# SCH_automated_chess_2024-11-14.net
KiCad netlist of a schematic drawn in EasyEDA
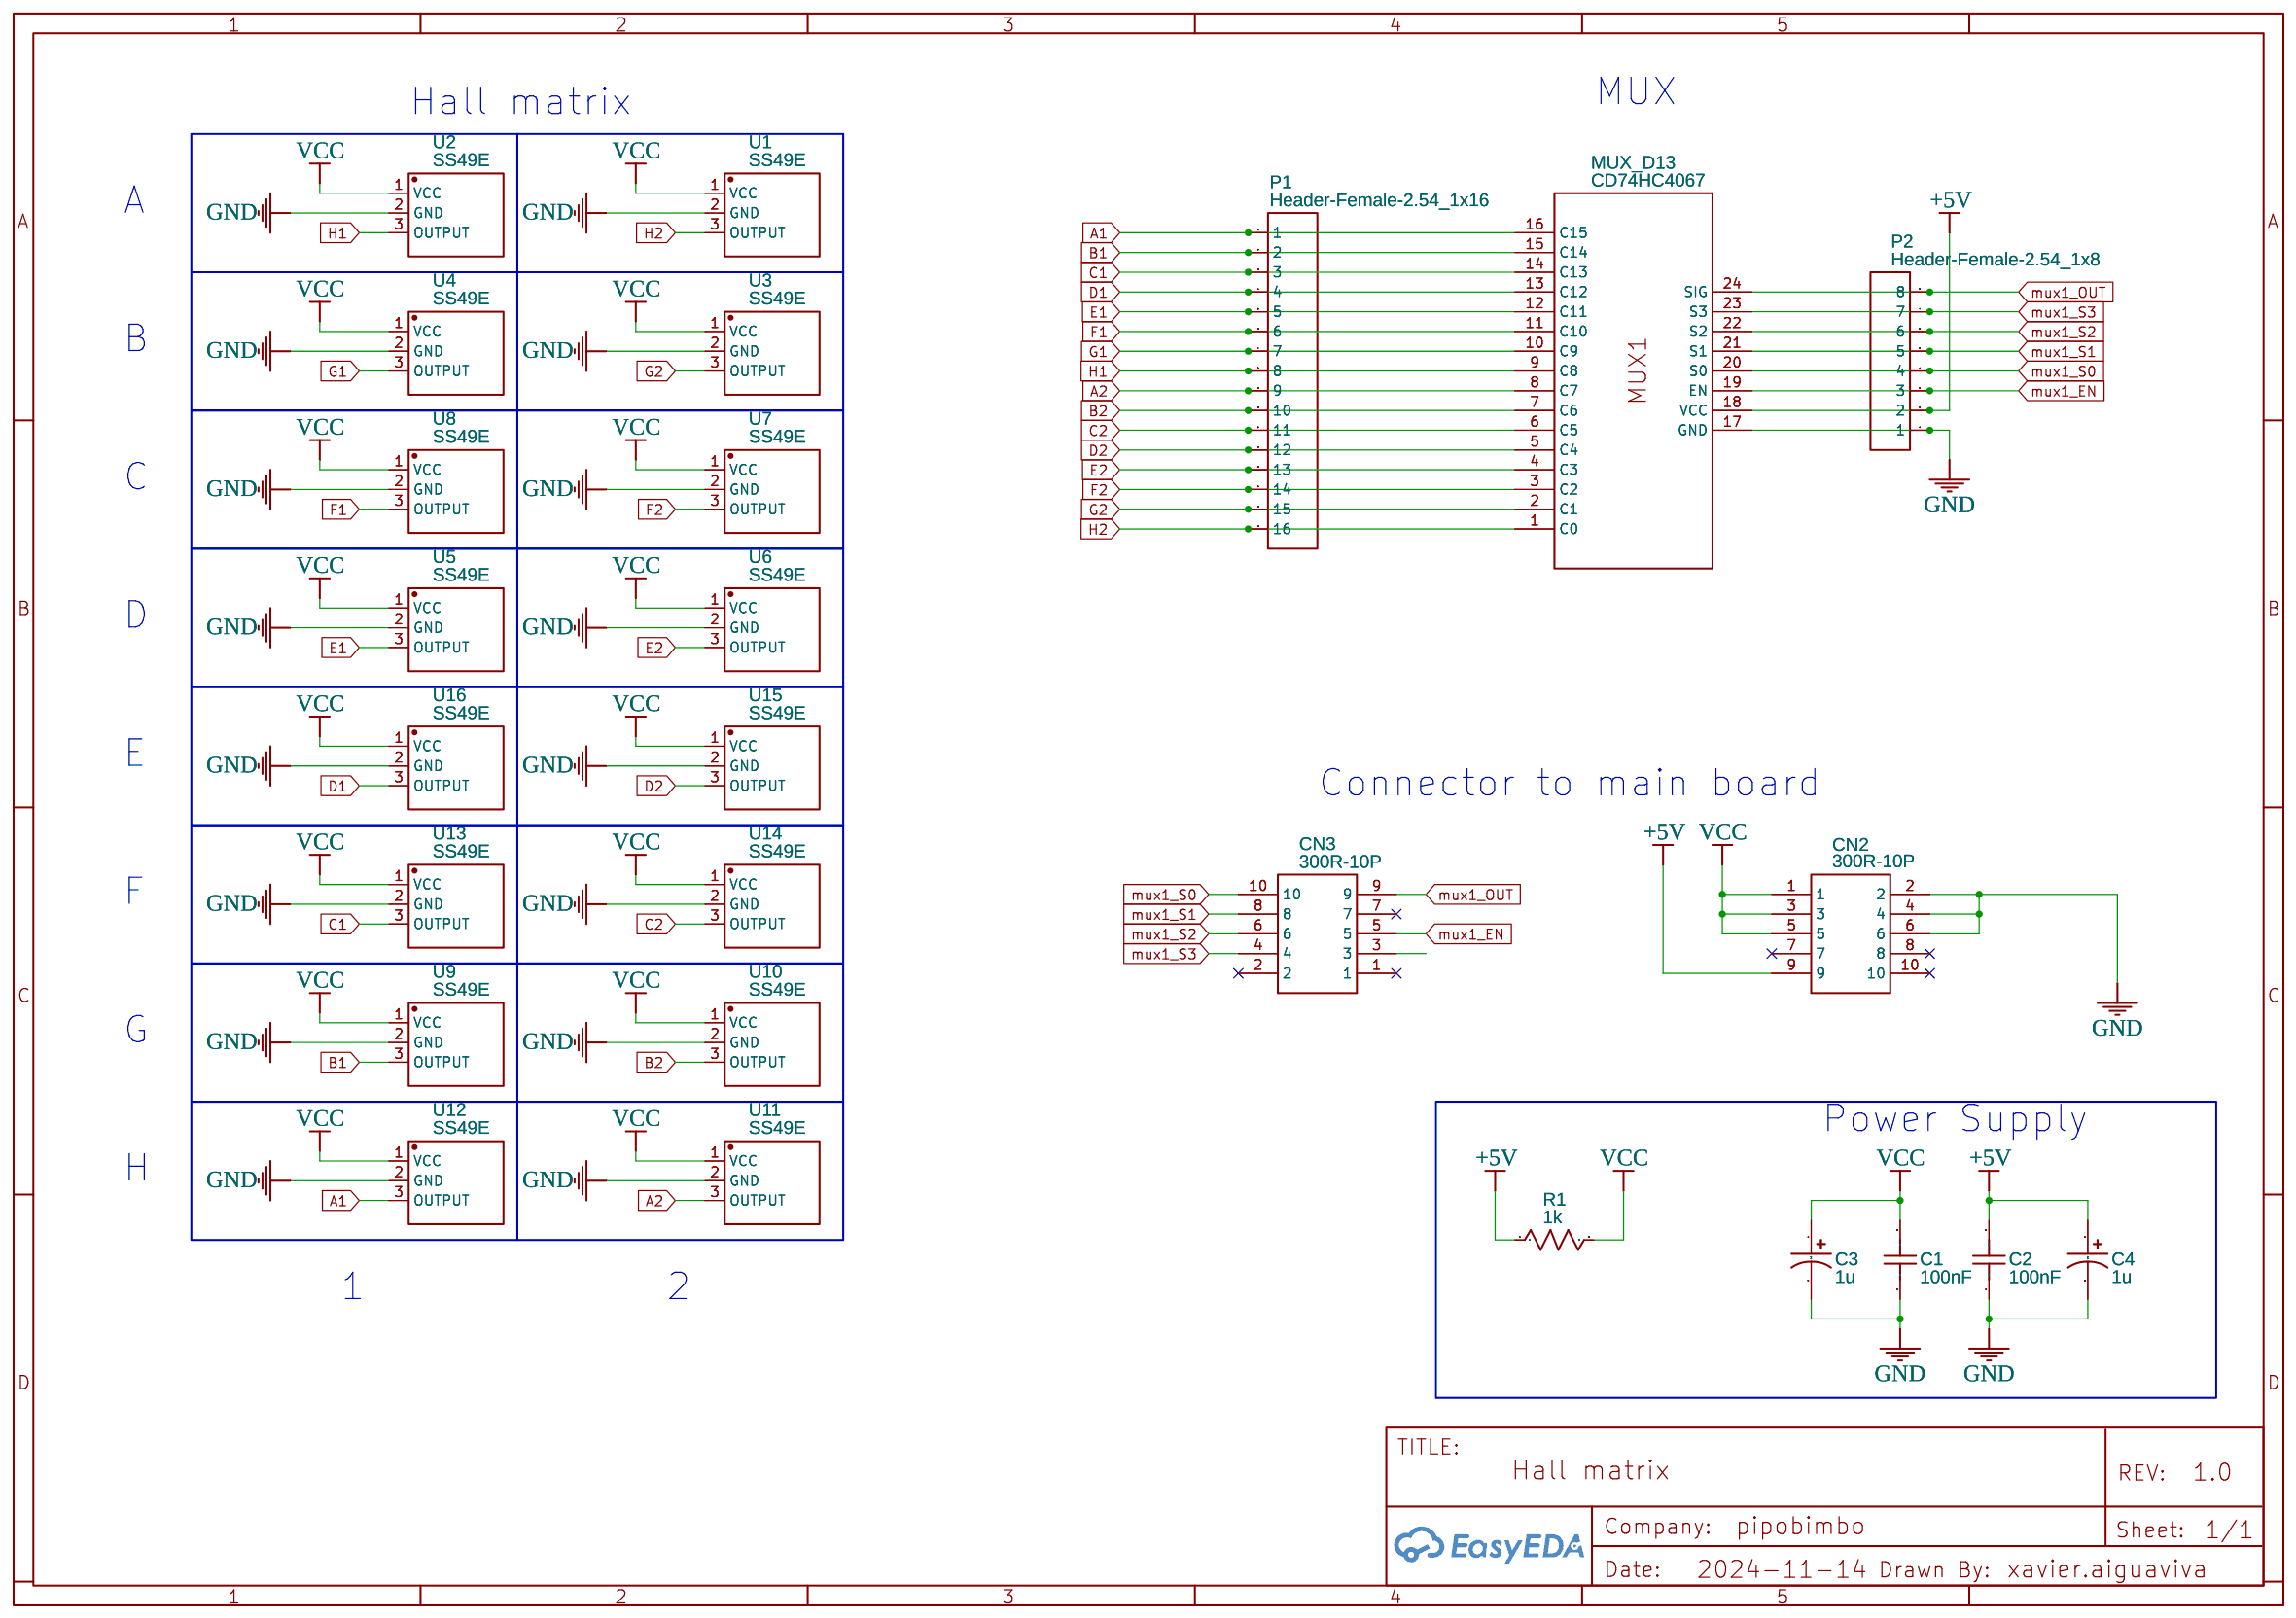
[diagram p0: schematic sheet]

(export (version "E")
  (design (tool "Eeschema 10.0.6"))
  (components
    (comp (ref "C1")
      (value "100nF")
      (fields
        (field (name "Manufacturer Part") "CC1H104MC1FD3F6C10MF")
        (field (name "Manufacturer") "Dersonic(德尔创)")
      )
      (libsource (lib "") (part "CC1H104MC1FD3F6C10MF"))
    )
    (comp (ref "C2")
      (value "100nF")
      (fields
        (field (name "Manufacturer Part") "CC1H104MC1FD3F6C10MF")
        (field (name "Manufacturer") "Dersonic(德尔创)")
      )
      (libsource (lib "") (part "CC1H104MC1FD3F6C10MF"))
    )
    (comp (ref "C3") (value "1u") (libsource (lib "") (part "C_Tan_SMD_D_US_1")))
    (comp (ref "C4") (value "1u") (libsource (lib "") (part "C_Tan_SMD_D_US")))
    (comp (ref "CN2")
      (value "300R-10P")
      (fields (field (name "Manufacturer Part") "B-3000R10P-0110") (field (name "Manufacturer") "Ckmtw(灿科盟)"))
      (libsource (lib "") (part "300R-10P_1"))
    )
    (comp (ref "CN3")
      (value "300R-10P")
      (fields (field (name "Manufacturer Part") "B-3000R10P-0110") (field (name "Manufacturer") "Ckmtw(灿科盟)"))
      (libsource (lib "") (part "300R-10P"))
    )
    (comp (ref "MUX_D13") (value "CD74HC4067") (libsource (lib "") (part "CD74HC4067")))
    (comp (ref "P1")
      (value "Header-Female-2.54_1x16")
      (fields (field (name "Manufacturer Part") "2.54-1*16P母") (field (name "Manufacturer") "BOOMELE(博穆精密)"))
      (libsource (lib "") (part "Header-Female-2.54_1x16"))
    )
    (comp (ref "P2")
      (value "Header-Female-2.54_1x8")
      (fields (field (name "Manufacturer Part") "2.54-1*8P母环保") (field (name "Manufacturer") "BOOMELE(博穆精密)"))
      (libsource (lib "") (part "Header-Female-2.54_1x8"))
    )
    (comp (ref "R1") (value "1k") (libsource (lib "") (part "R_1210_US")))
    (comp (ref "U1")
      (value "SS49E")
      (fields (field (name "Manufacturer") "Honeywell(霍尼韦尔)"))
      (libsource (lib "") (part "SS49E"))
    )
    (comp (ref "U2")
      (value "SS49E")
      (fields (field (name "Manufacturer") "Honeywell(霍尼韦尔)"))
      (libsource (lib "") (part "SS49E"))
    )
    (comp (ref "U3")
      (value "SS49E")
      (fields (field (name "Manufacturer") "Honeywell(霍尼韦尔)"))
      (libsource (lib "") (part "SS49E"))
    )
    (comp (ref "U4")
      (value "SS49E")
      (fields (field (name "Manufacturer") "Honeywell(霍尼韦尔)"))
      (libsource (lib "") (part "SS49E"))
    )
    (comp (ref "U5")
      (value "SS49E")
      (fields (field (name "Manufacturer") "Honeywell(霍尼韦尔)"))
      (libsource (lib "") (part "SS49E"))
    )
    (comp (ref "U6")
      (value "SS49E")
      (fields (field (name "Manufacturer") "Honeywell(霍尼韦尔)"))
      (libsource (lib "") (part "SS49E"))
    )
    (comp (ref "U7")
      (value "SS49E")
      (fields (field (name "Manufacturer") "Honeywell(霍尼韦尔)"))
      (libsource (lib "") (part "SS49E"))
    )
    (comp (ref "U8")
      (value "SS49E")
      (fields (field (name "Manufacturer") "Honeywell(霍尼韦尔)"))
      (libsource (lib "") (part "SS49E"))
    )
    (comp (ref "U9")
      (value "SS49E")
      (fields (field (name "Manufacturer") "Honeywell(霍尼韦尔)"))
      (libsource (lib "") (part "SS49E"))
    )
    (comp (ref "U10")
      (value "SS49E")
      (fields (field (name "Manufacturer") "Honeywell(霍尼韦尔)"))
      (libsource (lib "") (part "SS49E"))
    )
    (comp (ref "U11")
      (value "SS49E")
      (fields (field (name "Manufacturer") "Honeywell(霍尼韦尔)"))
      (libsource (lib "") (part "SS49E"))
    )
    (comp (ref "U12")
      (value "SS49E")
      (fields (field (name "Manufacturer") "Honeywell(霍尼韦尔)"))
      (libsource (lib "") (part "SS49E"))
    )
    (comp (ref "U13")
      (value "SS49E")
      (fields (field (name "Manufacturer") "Honeywell(霍尼韦尔)"))
      (libsource (lib "") (part "SS49E"))
    )
    (comp (ref "U14")
      (value "SS49E")
      (fields (field (name "Manufacturer") "Honeywell(霍尼韦尔)"))
      (libsource (lib "") (part "SS49E"))
    )
    (comp (ref "U15")
      (value "SS49E")
      (fields (field (name "Manufacturer") "Honeywell(霍尼韦尔)"))
      (libsource (lib "") (part "SS49E"))
    )
    (comp (ref "U16")
      (value "SS49E")
      (fields (field (name "Manufacturer") "Honeywell(霍尼韦尔)"))
      (libsource (lib "") (part "SS49E"))
    )
  )
  (nets
    (net (code "1") (name "+5V") (class "Default")
      (node (ref "C2") (pin "2") (pinfunction "2_2") (pintype "unspecified"))
      (node (ref "C4") (pin "1") (pinfunction "1_1") (pintype "unspecified"))
      (node (ref "CN2") (pin "9") (pinfunction "9_9") (pintype "unspecified"))
      (node (ref "MUX_D13") (pin "18") (pinfunction "VCC_18") (pintype "unspecified"))
      (node (ref "P2") (pin "2") (pinfunction "2_2") (pintype "input"))
      (node (ref "R1") (pin "1") (pinfunction "1_1") (pintype "unspecified"))
    )
    (net (code "2") (name "A1") (class "Default")
      (node (ref "MUX_D13") (pin "16") (pinfunction "C15_16") (pintype "unspecified"))
      (node (ref "P1") (pin "1") (pinfunction "1_1") (pintype "input"))
      (node (ref "U12") (pin "3") (pinfunction "OUTPUT_3") (pintype "unspecified"))
    )
    (net (code "3") (name "A2") (class "Default")
      (node (ref "MUX_D13") (pin "8") (pinfunction "C7_8") (pintype "unspecified"))
      (node (ref "P1") (pin "9") (pinfunction "9_9") (pintype "input"))
      (node (ref "U11") (pin "3") (pinfunction "OUTPUT_3") (pintype "unspecified"))
    )
    (net (code "4") (name "B1") (class "Default")
      (node (ref "MUX_D13") (pin "15") (pinfunction "C14_15") (pintype "unspecified"))
      (node (ref "P1") (pin "2") (pinfunction "2_2") (pintype "input"))
      (node (ref "U9") (pin "3") (pinfunction "OUTPUT_3") (pintype "unspecified"))
    )
    (net (code "5") (name "B2") (class "Default")
      (node (ref "MUX_D13") (pin "7") (pinfunction "C6_7") (pintype "unspecified"))
      (node (ref "P1") (pin "10") (pinfunction "10_10") (pintype "input"))
      (node (ref "U10") (pin "3") (pinfunction "OUTPUT_3") (pintype "unspecified"))
    )
    (net (code "6") (name "C1") (class "Default")
      (node (ref "MUX_D13") (pin "14") (pinfunction "C13_14") (pintype "unspecified"))
      (node (ref "P1") (pin "3") (pinfunction "3_3") (pintype "input"))
      (node (ref "U13") (pin "3") (pinfunction "OUTPUT_3") (pintype "unspecified"))
    )
    (net (code "7") (name "C2") (class "Default")
      (node (ref "MUX_D13") (pin "6") (pinfunction "C5_6") (pintype "unspecified"))
      (node (ref "P1") (pin "11") (pinfunction "11_11") (pintype "input"))
      (node (ref "U14") (pin "3") (pinfunction "OUTPUT_3") (pintype "unspecified"))
    )
    (net (code "8") (name "D1") (class "Default")
      (node (ref "MUX_D13") (pin "13") (pinfunction "C12_13") (pintype "unspecified"))
      (node (ref "P1") (pin "4") (pinfunction "4_4") (pintype "input"))
      (node (ref "U16") (pin "3") (pinfunction "OUTPUT_3") (pintype "unspecified"))
    )
    (net (code "9") (name "D2") (class "Default")
      (node (ref "MUX_D13") (pin "5") (pinfunction "C4_5") (pintype "unspecified"))
      (node (ref "P1") (pin "12") (pinfunction "12_12") (pintype "input"))
      (node (ref "U15") (pin "3") (pinfunction "OUTPUT_3") (pintype "unspecified"))
    )
    (net (code "10") (name "E1") (class "Default")
      (node (ref "MUX_D13") (pin "12") (pinfunction "C11_12") (pintype "unspecified"))
      (node (ref "P1") (pin "5") (pinfunction "5_5") (pintype "input"))
      (node (ref "U5") (pin "3") (pinfunction "OUTPUT_3") (pintype "unspecified"))
    )
    (net (code "11") (name "E2") (class "Default")
      (node (ref "MUX_D13") (pin "4") (pinfunction "C3_4") (pintype "unspecified"))
      (node (ref "P1") (pin "13") (pinfunction "13_13") (pintype "input"))
      (node (ref "U6") (pin "3") (pinfunction "OUTPUT_3") (pintype "unspecified"))
    )
    (net (code "12") (name "F1") (class "Default")
      (node (ref "MUX_D13") (pin "11") (pinfunction "C10_11") (pintype "unspecified"))
      (node (ref "P1") (pin "6") (pinfunction "6_6") (pintype "input"))
      (node (ref "U8") (pin "3") (pinfunction "OUTPUT_3") (pintype "unspecified"))
    )
    (net (code "13") (name "F2") (class "Default")
      (node (ref "MUX_D13") (pin "3") (pinfunction "C2_3") (pintype "unspecified"))
      (node (ref "P1") (pin "14") (pinfunction "14_14") (pintype "input"))
      (node (ref "U7") (pin "3") (pinfunction "OUTPUT_3") (pintype "unspecified"))
    )
    (net (code "14") (name "G1") (class "Default")
      (node (ref "MUX_D13") (pin "10") (pinfunction "C9_10") (pintype "unspecified"))
      (node (ref "P1") (pin "7") (pinfunction "7_7") (pintype "input"))
      (node (ref "U4") (pin "3") (pinfunction "OUTPUT_3") (pintype "unspecified"))
    )
    (net (code "15") (name "G2") (class "Default")
      (node (ref "MUX_D13") (pin "2") (pinfunction "C1_2") (pintype "unspecified"))
      (node (ref "P1") (pin "15") (pinfunction "15_15") (pintype "input"))
      (node (ref "U3") (pin "3") (pinfunction "OUTPUT_3") (pintype "unspecified"))
    )
    (net (code "16") (name "GND") (class "Default")
      (node (ref "C1") (pin "1") (pinfunction "1_1") (pintype "unspecified"))
      (node (ref "C2") (pin "1") (pinfunction "1_1") (pintype "unspecified"))
      (node (ref "C3") (pin "2") (pinfunction "2_2") (pintype "unspecified"))
      (node (ref "C4") (pin "2") (pinfunction "2_2") (pintype "unspecified"))
      (node (ref "CN2") (pin "2") (pinfunction "2_2") (pintype "unspecified"))
      (node (ref "CN2") (pin "4") (pinfunction "4_4") (pintype "unspecified"))
      (node (ref "CN2") (pin "6") (pinfunction "6_6") (pintype "unspecified"))
      (node (ref "MUX_D13") (pin "17") (pinfunction "GND_17") (pintype "unspecified"))
      (node (ref "P2") (pin "1") (pinfunction "1_1") (pintype "input"))
      (node (ref "U1") (pin "2") (pinfunction "GND_2") (pintype "unspecified"))
      (node (ref "U10") (pin "2") (pinfunction "GND_2") (pintype "unspecified"))
      (node (ref "U11") (pin "2") (pinfunction "GND_2") (pintype "unspecified"))
      (node (ref "U12") (pin "2") (pinfunction "GND_2") (pintype "unspecified"))
      (node (ref "U13") (pin "2") (pinfunction "GND_2") (pintype "unspecified"))
      (node (ref "U14") (pin "2") (pinfunction "GND_2") (pintype "unspecified"))
      (node (ref "U15") (pin "2") (pinfunction "GND_2") (pintype "unspecified"))
      (node (ref "U16") (pin "2") (pinfunction "GND_2") (pintype "unspecified"))
      (node (ref "U2") (pin "2") (pinfunction "GND_2") (pintype "unspecified"))
      (node (ref "U3") (pin "2") (pinfunction "GND_2") (pintype "unspecified"))
      (node (ref "U4") (pin "2") (pinfunction "GND_2") (pintype "unspecified"))
      (node (ref "U5") (pin "2") (pinfunction "GND_2") (pintype "unspecified"))
      (node (ref "U6") (pin "2") (pinfunction "GND_2") (pintype "unspecified"))
      (node (ref "U7") (pin "2") (pinfunction "GND_2") (pintype "unspecified"))
      (node (ref "U8") (pin "2") (pinfunction "GND_2") (pintype "unspecified"))
      (node (ref "U9") (pin "2") (pinfunction "GND_2") (pintype "unspecified"))
    )
    (net (code "17") (name "H1") (class "Default")
      (node (ref "MUX_D13") (pin "9") (pinfunction "C8_9") (pintype "unspecified"))
      (node (ref "P1") (pin "8") (pinfunction "8_8") (pintype "input"))
      (node (ref "U2") (pin "3") (pinfunction "OUTPUT_3") (pintype "unspecified"))
    )
    (net (code "18") (name "H2") (class "Default")
      (node (ref "MUX_D13") (pin "1") (pinfunction "C0_1") (pintype "unspecified"))
      (node (ref "P1") (pin "16") (pinfunction "16_16") (pintype "input"))
      (node (ref "U1") (pin "3") (pinfunction "OUTPUT_3") (pintype "unspecified"))
    )
    (net (code "19") (name "VCC") (class "Default")
      (node (ref "C1") (pin "2") (pinfunction "2_2") (pintype "unspecified"))
      (node (ref "C3") (pin "1") (pinfunction "1_1") (pintype "unspecified"))
      (node (ref "CN2") (pin "1") (pinfunction "1_1") (pintype "unspecified"))
      (node (ref "CN2") (pin "3") (pinfunction "3_3") (pintype "unspecified"))
      (node (ref "CN2") (pin "5") (pinfunction "5_5") (pintype "unspecified"))
      (node (ref "R1") (pin "2") (pinfunction "2_2") (pintype "unspecified"))
      (node (ref "U1") (pin "1") (pinfunction "VCC_1") (pintype "unspecified"))
      (node (ref "U10") (pin "1") (pinfunction "VCC_1") (pintype "unspecified"))
      (node (ref "U11") (pin "1") (pinfunction "VCC_1") (pintype "unspecified"))
      (node (ref "U12") (pin "1") (pinfunction "VCC_1") (pintype "unspecified"))
      (node (ref "U13") (pin "1") (pinfunction "VCC_1") (pintype "unspecified"))
      (node (ref "U14") (pin "1") (pinfunction "VCC_1") (pintype "unspecified"))
      (node (ref "U15") (pin "1") (pinfunction "VCC_1") (pintype "unspecified"))
      (node (ref "U16") (pin "1") (pinfunction "VCC_1") (pintype "unspecified"))
      (node (ref "U2") (pin "1") (pinfunction "VCC_1") (pintype "unspecified"))
      (node (ref "U3") (pin "1") (pinfunction "VCC_1") (pintype "unspecified"))
      (node (ref "U4") (pin "1") (pinfunction "VCC_1") (pintype "unspecified"))
      (node (ref "U5") (pin "1") (pinfunction "VCC_1") (pintype "unspecified"))
      (node (ref "U6") (pin "1") (pinfunction "VCC_1") (pintype "unspecified"))
      (node (ref "U7") (pin "1") (pinfunction "VCC_1") (pintype "unspecified"))
      (node (ref "U8") (pin "1") (pinfunction "VCC_1") (pintype "unspecified"))
      (node (ref "U9") (pin "1") (pinfunction "VCC_1") (pintype "unspecified"))
    )
    (net (code "20") (name "mux1_EN") (class "Default")
      (node (ref "CN3") (pin "5") (pinfunction "5_5") (pintype "unspecified"))
      (node (ref "MUX_D13") (pin "19") (pinfunction "EN_19") (pintype "unspecified"))
      (node (ref "P2") (pin "3") (pinfunction "3_3") (pintype "input"))
    )
    (net (code "21") (name "mux1_OUT") (class "Default")
      (node (ref "CN3") (pin "9") (pinfunction "9_9") (pintype "unspecified"))
      (node (ref "MUX_D13") (pin "24") (pinfunction "SIG_24") (pintype "unspecified"))
      (node (ref "P2") (pin "8") (pinfunction "8_8") (pintype "input"))
    )
    (net (code "22") (name "mux1_S0") (class "Default")
      (node (ref "CN3") (pin "10") (pinfunction "10_10") (pintype "unspecified"))
      (node (ref "MUX_D13") (pin "20") (pinfunction "S0_20") (pintype "unspecified"))
      (node (ref "P2") (pin "4") (pinfunction "4_4") (pintype "input"))
    )
    (net (code "23") (name "mux1_S1") (class "Default")
      (node (ref "CN3") (pin "8") (pinfunction "8_8") (pintype "unspecified"))
      (node (ref "MUX_D13") (pin "21") (pinfunction "S1_21") (pintype "unspecified"))
      (node (ref "P2") (pin "5") (pinfunction "5_5") (pintype "input"))
    )
    (net (code "24") (name "mux1_S2") (class "Default")
      (node (ref "CN3") (pin "6") (pinfunction "6_6") (pintype "unspecified"))
      (node (ref "MUX_D13") (pin "22") (pinfunction "S2_22") (pintype "unspecified"))
      (node (ref "P2") (pin "6") (pinfunction "6_6") (pintype "input"))
    )
    (net (code "25") (name "mux1_S3") (class "Default")
      (node (ref "CN3") (pin "4") (pinfunction "4_4") (pintype "unspecified"))
      (node (ref "MUX_D13") (pin "23") (pinfunction "S3_23") (pintype "unspecified"))
      (node (ref "P2") (pin "7") (pinfunction "7_7") (pintype "input"))
    )
    (net (code "26") (name "unconnected-(CN2-Pad7)") (class "Default")
      (node (ref "CN2") (pin "7") (pinfunction "7_7") (pintype "unspecified+no_connect"))
    )
    (net (code "27") (name "unconnected-(CN2-Pad8)") (class "Default")
      (node (ref "CN2") (pin "8") (pinfunction "8_8") (pintype "unspecified+no_connect"))
    )
    (net (code "28") (name "unconnected-(CN2-Pad10)") (class "Default")
      (node (ref "CN2") (pin "10") (pinfunction "10_10") (pintype "unspecified+no_connect"))
    )
    (net (code "29") (name "unconnected-(CN3-Pad1)") (class "Default")
      (node (ref "CN3") (pin "1") (pinfunction "1_1") (pintype "unspecified+no_connect"))
    )
    (net (code "30") (name "unconnected-(CN3-Pad2)") (class "Default")
      (node (ref "CN3") (pin "2") (pinfunction "2_2") (pintype "unspecified+no_connect"))
    )
    (net (code "31") (name "unconnected-(CN3-Pad3)") (class "Default")
      (node (ref "CN3") (pin "3") (pinfunction "3_3") (pintype "unspecified"))
    )
    (net (code "32") (name "unconnected-(CN3-Pad7)") (class "Default")
      (node (ref "CN3") (pin "7") (pinfunction "7_7") (pintype "unspecified+no_connect"))
    )
  )
)
